# Isolate_IO_v_1.net
KiCad netlist of a schematic drawn in EAGLE
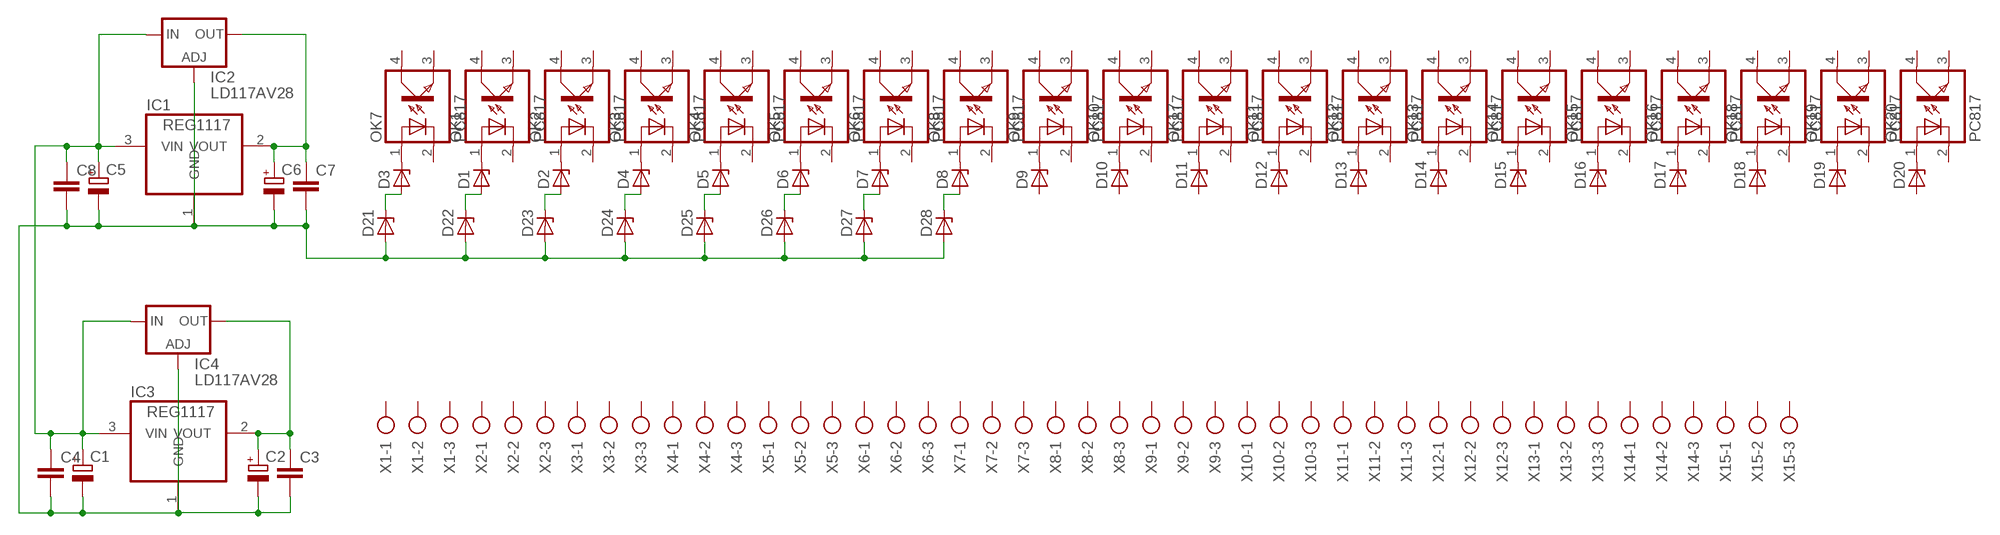
[diagram p0: schematic, sheet 1]

(export (version "E")
  (design (tool "Eeschema 10.0.6"))
  (components
    (comp (ref "C1")
      (value "CPOL-EUE2.5-5")
      (footprint "eagle-import:E2,5-5")
      (libsource (lib "eagle-import") (part "CPOL-EUE2.5-5"))
    )
    (comp (ref "C2")
      (value "CPOL-EUE3.5-10")
      (footprint "eagle-import:E3,5-10")
      (libsource (lib "eagle-import") (part "CPOL-EUE3.5-10"))
    )
    (comp (ref "C3")
      (value "C-EU025-030X050")
      (footprint "eagle-import:C025-030X050")
      (libsource (lib "eagle-import") (part "C-EU025-030X050"))
    )
    (comp (ref "C4")
      (value "C-EU025-030X050")
      (footprint "eagle-import:C025-030X050")
      (libsource (lib "eagle-import") (part "C-EU025-030X050"))
    )
    (comp (ref "C5")
      (value "CPOL-EUE2.5-5")
      (footprint "eagle-import:E2,5-5")
      (libsource (lib "eagle-import") (part "CPOL-EUE2.5-5"))
    )
    (comp (ref "C6")
      (value "CPOL-EUE3.5-10")
      (footprint "eagle-import:E3,5-10")
      (libsource (lib "eagle-import") (part "CPOL-EUE3.5-10"))
    )
    (comp (ref "C7")
      (value "C-EU025-030X050")
      (footprint "eagle-import:C025-030X050")
      (libsource (lib "eagle-import") (part "C-EU025-030X050"))
    )
    (comp (ref "C8")
      (value "C-EU025-030X050")
      (footprint "eagle-import:C025-030X050")
      (libsource (lib "eagle-import") (part "C-EU025-030X050"))
    )
    (comp (ref "D1")
      (value "ZENER-DIODEZD-2.5")
      (footprint "eagle-import:ZDIO-2.5")
      (libsource (lib "eagle-import") (part "ZENER-DIODEZD-2.5"))
    )
    (comp (ref "D2")
      (value "ZENER-DIODEZD-2.5")
      (footprint "eagle-import:ZDIO-2.5")
      (libsource (lib "eagle-import") (part "ZENER-DIODEZD-2.5"))
    )
    (comp (ref "D3")
      (value "ZENER-DIODEZD-2.5")
      (footprint "eagle-import:ZDIO-2.5")
      (libsource (lib "eagle-import") (part "ZENER-DIODEZD-2.5"))
    )
    (comp (ref "D4")
      (value "ZENER-DIODEZD-2.5")
      (footprint "eagle-import:ZDIO-2.5")
      (libsource (lib "eagle-import") (part "ZENER-DIODEZD-2.5"))
    )
    (comp (ref "D5")
      (value "ZENER-DIODEZD-2.5")
      (footprint "eagle-import:ZDIO-2.5")
      (libsource (lib "eagle-import") (part "ZENER-DIODEZD-2.5"))
    )
    (comp (ref "D6")
      (value "ZENER-DIODEZD-2.5")
      (footprint "eagle-import:ZDIO-2.5")
      (libsource (lib "eagle-import") (part "ZENER-DIODEZD-2.5"))
    )
    (comp (ref "D7")
      (value "ZENER-DIODEZD-2.5")
      (footprint "eagle-import:ZDIO-2.5")
      (libsource (lib "eagle-import") (part "ZENER-DIODEZD-2.5"))
    )
    (comp (ref "D8")
      (value "ZENER-DIODEZD-2.5")
      (footprint "eagle-import:ZDIO-2.5")
      (libsource (lib "eagle-import") (part "ZENER-DIODEZD-2.5"))
    )
    (comp (ref "D9")
      (value "ZENER-DIODEZD-2.5")
      (footprint "eagle-import:ZDIO-2.5")
      (libsource (lib "eagle-import") (part "ZENER-DIODEZD-2.5"))
    )
    (comp (ref "D10")
      (value "ZENER-DIODEZD-2.5")
      (footprint "eagle-import:ZDIO-2.5")
      (libsource (lib "eagle-import") (part "ZENER-DIODEZD-2.5"))
    )
    (comp (ref "D11")
      (value "ZENER-DIODEZD-2.5")
      (footprint "eagle-import:ZDIO-2.5")
      (libsource (lib "eagle-import") (part "ZENER-DIODEZD-2.5"))
    )
    (comp (ref "D12")
      (value "ZENER-DIODEZD-2.5")
      (footprint "eagle-import:ZDIO-2.5")
      (libsource (lib "eagle-import") (part "ZENER-DIODEZD-2.5"))
    )
    (comp (ref "D13")
      (value "ZENER-DIODEZD-2.5")
      (footprint "eagle-import:ZDIO-2.5")
      (libsource (lib "eagle-import") (part "ZENER-DIODEZD-2.5"))
    )
    (comp (ref "D14")
      (value "ZENER-DIODEZD-2.5")
      (footprint "eagle-import:ZDIO-2.5")
      (libsource (lib "eagle-import") (part "ZENER-DIODEZD-2.5"))
    )
    (comp (ref "D15")
      (value "ZENER-DIODEZD-2.5")
      (footprint "eagle-import:ZDIO-2.5")
      (libsource (lib "eagle-import") (part "ZENER-DIODEZD-2.5"))
    )
    (comp (ref "D16")
      (value "ZENER-DIODEZD-2.5")
      (footprint "eagle-import:ZDIO-2.5")
      (libsource (lib "eagle-import") (part "ZENER-DIODEZD-2.5"))
    )
    (comp (ref "D17")
      (value "ZENER-DIODEZD-2.5")
      (footprint "eagle-import:ZDIO-2.5")
      (libsource (lib "eagle-import") (part "ZENER-DIODEZD-2.5"))
    )
    (comp (ref "D18")
      (value "ZENER-DIODEZD-2.5")
      (footprint "eagle-import:ZDIO-2.5")
      (libsource (lib "eagle-import") (part "ZENER-DIODEZD-2.5"))
    )
    (comp (ref "D19")
      (value "ZENER-DIODEZD-2.5")
      (footprint "eagle-import:ZDIO-2.5")
      (libsource (lib "eagle-import") (part "ZENER-DIODEZD-2.5"))
    )
    (comp (ref "D20")
      (value "ZENER-DIODEZD-2.5")
      (footprint "eagle-import:ZDIO-2.5")
      (libsource (lib "eagle-import") (part "ZENER-DIODEZD-2.5"))
    )
    (comp (ref "D21")
      (value "ZENER-DIODEZD-2.5")
      (footprint "eagle-import:ZDIO-2.5")
      (libsource (lib "eagle-import") (part "ZENER-DIODEZD-2.5"))
    )
    (comp (ref "D22")
      (value "ZENER-DIODEZD-2.5")
      (footprint "eagle-import:ZDIO-2.5")
      (libsource (lib "eagle-import") (part "ZENER-DIODEZD-2.5"))
    )
    (comp (ref "D23")
      (value "ZENER-DIODEZD-2.5")
      (footprint "eagle-import:ZDIO-2.5")
      (libsource (lib "eagle-import") (part "ZENER-DIODEZD-2.5"))
    )
    (comp (ref "D24")
      (value "ZENER-DIODEZD-2.5")
      (footprint "eagle-import:ZDIO-2.5")
      (libsource (lib "eagle-import") (part "ZENER-DIODEZD-2.5"))
    )
    (comp (ref "D25")
      (value "ZENER-DIODEZD-2.5")
      (footprint "eagle-import:ZDIO-2.5")
      (libsource (lib "eagle-import") (part "ZENER-DIODEZD-2.5"))
    )
    (comp (ref "D26")
      (value "ZENER-DIODEZD-2.5")
      (footprint "eagle-import:ZDIO-2.5")
      (libsource (lib "eagle-import") (part "ZENER-DIODEZD-2.5"))
    )
    (comp (ref "D27")
      (value "ZENER-DIODEZD-2.5")
      (footprint "eagle-import:ZDIO-2.5")
      (libsource (lib "eagle-import") (part "ZENER-DIODEZD-2.5"))
    )
    (comp (ref "D28")
      (value "ZENER-DIODEZD-2.5")
      (footprint "eagle-import:ZDIO-2.5")
      (libsource (lib "eagle-import") (part "ZENER-DIODEZD-2.5"))
    )
    (comp (ref "IC1")
      (value "REG1117")
      (footprint "eagle-import:SOT223")
      (libsource (lib "eagle-import") (part "REG1117"))
    )
    (comp (ref "IC2")
      (value "LD117AV28")
      (footprint "eagle-import:TO220L1")
      (libsource (lib "eagle-import") (part "LD117A?V28"))
    )
    (comp (ref "IC3")
      (value "REG1117")
      (footprint "eagle-import:SOT223")
      (libsource (lib "eagle-import") (part "REG1117"))
    )
    (comp (ref "IC4")
      (value "LD117AV28")
      (footprint "eagle-import:TO220L1")
      (libsource (lib "eagle-import") (part "LD117A?V28"))
    )
    (comp (ref "OK1")
      (value "PC817")
      (footprint "eagle-import:DIL04")
      (fields (field (name "MPN") "PC817X4J000F"))
      (libsource (lib "eagle-import") (part "PC817"))
    )
    (comp (ref "OK2")
      (value "PC817")
      (footprint "eagle-import:DIL04")
      (fields (field (name "MPN") "PC817X4J000F"))
      (libsource (lib "eagle-import") (part "PC817"))
    )
    (comp (ref "OK3")
      (value "PC817")
      (footprint "eagle-import:DIL04")
      (fields (field (name "MPN") "PC817X4J000F"))
      (libsource (lib "eagle-import") (part "PC817"))
    )
    (comp (ref "OK4")
      (value "PC817")
      (footprint "eagle-import:DIL04")
      (fields (field (name "MPN") "PC817X4J000F"))
      (libsource (lib "eagle-import") (part "PC817"))
    )
    (comp (ref "OK5")
      (value "PC817")
      (footprint "eagle-import:DIL04")
      (fields (field (name "MPN") "PC817X4J000F"))
      (libsource (lib "eagle-import") (part "PC817"))
    )
    (comp (ref "OK6")
      (value "PC817")
      (footprint "eagle-import:DIL04")
      (fields (field (name "MPN") "PC817X4J000F"))
      (libsource (lib "eagle-import") (part "PC817"))
    )
    (comp (ref "OK7")
      (value "PC817")
      (footprint "eagle-import:DIL04")
      (fields (field (name "MPN") "PC817X4J000F"))
      (libsource (lib "eagle-import") (part "PC817"))
    )
    (comp (ref "OK8")
      (value "PC817")
      (footprint "eagle-import:DIL04")
      (fields (field (name "MPN") "PC817X4J000F"))
      (libsource (lib "eagle-import") (part "PC817"))
    )
    (comp (ref "OK9")
      (value "PC817")
      (footprint "eagle-import:DIL04")
      (fields (field (name "MPN") "PC817X4J000F"))
      (libsource (lib "eagle-import") (part "PC817"))
    )
    (comp (ref "OK10")
      (value "PC817")
      (footprint "eagle-import:DIL04")
      (fields (field (name "MPN") "PC817X4J000F"))
      (libsource (lib "eagle-import") (part "PC817"))
    )
    (comp (ref "OK11")
      (value "PC817")
      (footprint "eagle-import:DIL04")
      (fields (field (name "MPN") "PC817X4J000F"))
      (libsource (lib "eagle-import") (part "PC817"))
    )
    (comp (ref "OK12")
      (value "PC817")
      (footprint "eagle-import:DIL04")
      (fields (field (name "MPN") "PC817X4J000F"))
      (libsource (lib "eagle-import") (part "PC817"))
    )
    (comp (ref "OK13")
      (value "PC817")
      (footprint "eagle-import:DIL04")
      (fields (field (name "MPN") "PC817X4J000F"))
      (libsource (lib "eagle-import") (part "PC817"))
    )
    (comp (ref "OK14")
      (value "PC817")
      (footprint "eagle-import:DIL04")
      (fields (field (name "MPN") "PC817X4J000F"))
      (libsource (lib "eagle-import") (part "PC817"))
    )
    (comp (ref "OK15")
      (value "PC817")
      (footprint "eagle-import:DIL04")
      (fields (field (name "MPN") "PC817X4J000F"))
      (libsource (lib "eagle-import") (part "PC817"))
    )
    (comp (ref "OK16")
      (value "PC817")
      (footprint "eagle-import:DIL04")
      (fields (field (name "MPN") "PC817X4J000F"))
      (libsource (lib "eagle-import") (part "PC817"))
    )
    (comp (ref "OK17")
      (value "PC817")
      (footprint "eagle-import:DIL04")
      (fields (field (name "MPN") "PC817X4J000F"))
      (libsource (lib "eagle-import") (part "PC817"))
    )
    (comp (ref "OK18")
      (value "PC817")
      (footprint "eagle-import:DIL04")
      (fields (field (name "MPN") "PC817X4J000F"))
      (libsource (lib "eagle-import") (part "PC817"))
    )
    (comp (ref "OK19")
      (value "PC817")
      (footprint "eagle-import:DIL04")
      (fields (field (name "MPN") "PC817X4J000F"))
      (libsource (lib "eagle-import") (part "PC817"))
    )
    (comp (ref "OK20")
      (value "PC817")
      (footprint "eagle-import:DIL04")
      (fields (field (name "MPN") "PC817X4J000F"))
      (libsource (lib "eagle-import") (part "PC817"))
    )
    (comp (ref "X1")
      (value "AK500/3")
      (footprint "eagle-import:AK500_3")
      (libsource (lib "eagle-import") (part "AK500/3"))
    )
    (comp (ref "X2")
      (value "AK500/3")
      (footprint "eagle-import:AK500_3")
      (libsource (lib "eagle-import") (part "AK500/3"))
    )
    (comp (ref "X3")
      (value "AK500/3")
      (footprint "eagle-import:AK500_3")
      (libsource (lib "eagle-import") (part "AK500/3"))
    )
    (comp (ref "X4")
      (value "AK500/3")
      (footprint "eagle-import:AK500_3")
      (libsource (lib "eagle-import") (part "AK500/3"))
    )
    (comp (ref "X5")
      (value "AK500/3")
      (footprint "eagle-import:AK500_3")
      (libsource (lib "eagle-import") (part "AK500/3"))
    )
    (comp (ref "X6")
      (value "AK500/3")
      (footprint "eagle-import:AK500_3")
      (libsource (lib "eagle-import") (part "AK500/3"))
    )
    (comp (ref "X7")
      (value "AK500/3")
      (footprint "eagle-import:AK500_3")
      (libsource (lib "eagle-import") (part "AK500/3"))
    )
    (comp (ref "X8")
      (value "AK500/3")
      (footprint "eagle-import:AK500_3")
      (libsource (lib "eagle-import") (part "AK500/3"))
    )
    (comp (ref "X9")
      (value "AK500/3")
      (footprint "eagle-import:AK500_3")
      (libsource (lib "eagle-import") (part "AK500/3"))
    )
    (comp (ref "X10")
      (value "AK500/3")
      (footprint "eagle-import:AK500_3")
      (libsource (lib "eagle-import") (part "AK500/3"))
    )
    (comp (ref "X11")
      (value "AK500/3")
      (footprint "eagle-import:AK500_3")
      (libsource (lib "eagle-import") (part "AK500/3"))
    )
    (comp (ref "X12")
      (value "AK500/3")
      (footprint "eagle-import:AK500_3")
      (libsource (lib "eagle-import") (part "AK500/3"))
    )
    (comp (ref "X13")
      (value "AK500/3")
      (footprint "eagle-import:AK500_3")
      (libsource (lib "eagle-import") (part "AK500/3"))
    )
    (comp (ref "X14")
      (value "AK500/3")
      (footprint "eagle-import:AK500_3")
      (libsource (lib "eagle-import") (part "AK500/3"))
    )
    (comp (ref "X15")
      (value "AK500/3")
      (footprint "eagle-import:AK500_3")
      (libsource (lib "eagle-import") (part "AK500/3"))
    )
  )
  (nets
    (net (code "1") (name "Net-(D1-PadA)") (class "Default")
      (node (ref "D1") (pin "A") (pinfunction "A_A") (pintype "passive"))
      (node (ref "D22") (pin "C") (pinfunction "C_C") (pintype "passive"))
    )
    (net (code "2") (name "Net-(D2-PadA)") (class "Default")
      (node (ref "D2") (pin "A") (pinfunction "A_A") (pintype "passive"))
      (node (ref "D23") (pin "C") (pinfunction "C_C") (pintype "passive"))
    )
    (net (code "3") (name "Net-(D21-PadC)") (class "Default")
      (node (ref "D21") (pin "C") (pinfunction "C_C") (pintype "passive"))
      (node (ref "D3") (pin "A") (pinfunction "A_A") (pintype "passive"))
    )
    (net (code "4") (name "Net-(D24-PadC)") (class "Default")
      (node (ref "D24") (pin "C") (pinfunction "C_C") (pintype "passive"))
      (node (ref "D4") (pin "A") (pinfunction "A_A") (pintype "passive"))
    )
    (net (code "5") (name "Net-(D25-PadC)") (class "Default")
      (node (ref "D25") (pin "C") (pinfunction "C_C") (pintype "passive"))
      (node (ref "D5") (pin "A") (pinfunction "A_A") (pintype "passive"))
    )
    (net (code "6") (name "Net-(D26-PadC)") (class "Default")
      (node (ref "D26") (pin "C") (pinfunction "C_C") (pintype "passive"))
      (node (ref "D6") (pin "A") (pinfunction "A_A") (pintype "passive"))
    )
    (net (code "7") (name "Net-(D27-PadC)") (class "Default")
      (node (ref "D27") (pin "C") (pinfunction "C_C") (pintype "passive"))
      (node (ref "D7") (pin "A") (pinfunction "A_A") (pintype "passive"))
    )
    (net (code "8") (name "Net-(D28-PadC)") (class "Default")
      (node (ref "D28") (pin "C") (pinfunction "C_C") (pintype "passive"))
      (node (ref "D8") (pin "A") (pinfunction "A_A") (pintype "passive"))
    )
    (net (code "9") (name "Net-(IC1-GND)") (class "Default")
      (node (ref "C1") (pin "-") (pinfunction "-_-") (pintype "passive"))
      (node (ref "C2") (pin "-") (pinfunction "-_-") (pintype "passive"))
      (node (ref "C3") (pin "2") (pinfunction "2_2") (pintype "passive"))
      (node (ref "C4") (pin "2") (pinfunction "2_2") (pintype "passive"))
      (node (ref "C5") (pin "-") (pinfunction "-_-") (pintype "passive"))
      (node (ref "C6") (pin "-") (pinfunction "-_-") (pintype "passive"))
      (node (ref "C7") (pin "2") (pinfunction "2_2") (pintype "passive"))
      (node (ref "C8") (pin "2") (pinfunction "2_2") (pintype "passive"))
      (node (ref "D21") (pin "A") (pinfunction "A_A") (pintype "passive"))
      (node (ref "D22") (pin "A") (pinfunction "A_A") (pintype "passive"))
      (node (ref "D23") (pin "A") (pinfunction "A_A") (pintype "passive"))
      (node (ref "D24") (pin "A") (pinfunction "A_A") (pintype "passive"))
      (node (ref "D25") (pin "A") (pinfunction "A_A") (pintype "passive"))
      (node (ref "D26") (pin "A") (pinfunction "A_A") (pintype "passive"))
      (node (ref "D27") (pin "A") (pinfunction "A_A") (pintype "passive"))
      (node (ref "D28") (pin "A") (pinfunction "A_A") (pintype "passive"))
      (node (ref "IC1") (pin "1") (pinfunction "GND_1") (pintype "power_in"))
      (node (ref "IC2") (pin "1") (pinfunction "ADJ_1") (pintype "input"))
      (node (ref "IC3") (pin "1") (pinfunction "GND_1") (pintype "power_in"))
      (node (ref "IC4") (pin "1") (pinfunction "ADJ_1") (pintype "input"))
    )
    (net (code "10") (name "Net-(IC1-VIN)") (class "Default")
      (node (ref "C1") (pin "+") (pinfunction "+_+") (pintype "passive"))
      (node (ref "C4") (pin "1") (pinfunction "1_1") (pintype "passive"))
      (node (ref "C5") (pin "+") (pinfunction "+_+") (pintype "passive"))
      (node (ref "C8") (pin "1") (pinfunction "1_1") (pintype "passive"))
      (node (ref "IC1") (pin "3") (pinfunction "VIN_3") (pintype "input"))
      (node (ref "IC2") (pin "3") (pinfunction "IN_3") (pintype "input"))
      (node (ref "IC3") (pin "3") (pinfunction "VIN_3") (pintype "input"))
      (node (ref "IC4") (pin "3") (pinfunction "IN_3") (pintype "input"))
    )
    (net (code "11") (name "Net-(IC1-VOUT)") (class "Default")
      (node (ref "C6") (pin "+") (pinfunction "+_+") (pintype "passive"))
      (node (ref "C7") (pin "1") (pinfunction "1_1") (pintype "passive"))
      (node (ref "IC1") (pin "2") (pinfunction "VOUT_2") (pintype "output"))
      (node (ref "IC2") (pin "2") (pinfunction "OUT_2") (pintype "passive"))
    )
    (net (code "12") (name "Net-(IC3-VOUT)") (class "Default")
      (node (ref "C2") (pin "+") (pinfunction "+_+") (pintype "passive"))
      (node (ref "C3") (pin "1") (pinfunction "1_1") (pintype "passive"))
      (node (ref "IC3") (pin "2") (pinfunction "VOUT_2") (pintype "output"))
      (node (ref "IC4") (pin "2") (pinfunction "OUT_2") (pintype "passive"))
    )
    (net (code "13") (name "Net-(OK1-A)") (class "Default")
      (node (ref "D1") (pin "C") (pinfunction "C_C") (pintype "passive"))
      (node (ref "OK1") (pin "1") (pinfunction "A_1") (pintype "passive"))
    )
    (net (code "14") (name "Net-(OK2-A)") (class "Default")
      (node (ref "D2") (pin "C") (pinfunction "C_C") (pintype "passive"))
      (node (ref "OK2") (pin "1") (pinfunction "A_1") (pintype "passive"))
    )
    (net (code "15") (name "Net-(OK3-A)") (class "Default")
      (node (ref "D4") (pin "C") (pinfunction "C_C") (pintype "passive"))
      (node (ref "OK3") (pin "1") (pinfunction "A_1") (pintype "passive"))
    )
    (net (code "16") (name "Net-(OK4-A)") (class "Default")
      (node (ref "D5") (pin "C") (pinfunction "C_C") (pintype "passive"))
      (node (ref "OK4") (pin "1") (pinfunction "A_1") (pintype "passive"))
    )
    (net (code "17") (name "Net-(OK5-A)") (class "Default")
      (node (ref "D6") (pin "C") (pinfunction "C_C") (pintype "passive"))
      (node (ref "OK5") (pin "1") (pinfunction "A_1") (pintype "passive"))
    )
    (net (code "18") (name "Net-(OK6-A)") (class "Default")
      (node (ref "D7") (pin "C") (pinfunction "C_C") (pintype "passive"))
      (node (ref "OK6") (pin "1") (pinfunction "A_1") (pintype "passive"))
    )
    (net (code "19") (name "Net-(OK7-A)") (class "Default")
      (node (ref "D3") (pin "C") (pinfunction "C_C") (pintype "passive"))
      (node (ref "OK7") (pin "1") (pinfunction "A_1") (pintype "passive"))
    )
    (net (code "20") (name "Net-(OK8-A)") (class "Default")
      (node (ref "D8") (pin "C") (pinfunction "C_C") (pintype "passive"))
      (node (ref "OK8") (pin "1") (pinfunction "A_1") (pintype "passive"))
    )
    (net (code "21") (name "Net-(OK9-A)") (class "Default")
      (node (ref "D9") (pin "C") (pinfunction "C_C") (pintype "passive"))
      (node (ref "OK9") (pin "1") (pinfunction "A_1") (pintype "passive"))
    )
    (net (code "22") (name "Net-(OK10-A)") (class "Default")
      (node (ref "D10") (pin "C") (pinfunction "C_C") (pintype "passive"))
      (node (ref "OK10") (pin "1") (pinfunction "A_1") (pintype "passive"))
    )
    (net (code "23") (name "Net-(OK11-A)") (class "Default")
      (node (ref "D12") (pin "C") (pinfunction "C_C") (pintype "passive"))
      (node (ref "OK11") (pin "1") (pinfunction "A_1") (pintype "passive"))
    )
    (net (code "24") (name "Net-(OK12-A)") (class "Default")
      (node (ref "D13") (pin "C") (pinfunction "C_C") (pintype "passive"))
      (node (ref "OK12") (pin "1") (pinfunction "A_1") (pintype "passive"))
    )
    (net (code "25") (name "Net-(OK13-A)") (class "Default")
      (node (ref "D14") (pin "C") (pinfunction "C_C") (pintype "passive"))
      (node (ref "OK13") (pin "1") (pinfunction "A_1") (pintype "passive"))
    )
    (net (code "26") (name "Net-(OK14-A)") (class "Default")
      (node (ref "D15") (pin "C") (pinfunction "C_C") (pintype "passive"))
      (node (ref "OK14") (pin "1") (pinfunction "A_1") (pintype "passive"))
    )
    (net (code "27") (name "Net-(OK15-A)") (class "Default")
      (node (ref "D16") (pin "C") (pinfunction "C_C") (pintype "passive"))
      (node (ref "OK15") (pin "1") (pinfunction "A_1") (pintype "passive"))
    )
    (net (code "28") (name "Net-(OK16-A)") (class "Default")
      (node (ref "D17") (pin "C") (pinfunction "C_C") (pintype "passive"))
      (node (ref "OK16") (pin "1") (pinfunction "A_1") (pintype "passive"))
    )
    (net (code "29") (name "Net-(OK17-A)") (class "Default")
      (node (ref "D11") (pin "C") (pinfunction "C_C") (pintype "passive"))
      (node (ref "OK17") (pin "1") (pinfunction "A_1") (pintype "passive"))
    )
    (net (code "30") (name "Net-(OK18-A)") (class "Default")
      (node (ref "D18") (pin "C") (pinfunction "C_C") (pintype "passive"))
      (node (ref "OK18") (pin "1") (pinfunction "A_1") (pintype "passive"))
    )
    (net (code "31") (name "Net-(OK19-A)") (class "Default")
      (node (ref "D19") (pin "C") (pinfunction "C_C") (pintype "passive"))
      (node (ref "OK19") (pin "1") (pinfunction "A_1") (pintype "passive"))
    )
    (net (code "32") (name "Net-(OK20-A)") (class "Default")
      (node (ref "D20") (pin "C") (pinfunction "C_C") (pintype "passive"))
      (node (ref "OK20") (pin "1") (pinfunction "A_1") (pintype "passive"))
    )
    (net (code "33") (name "unconnected-(D9-PadA)") (class "Default")
      (node (ref "D9") (pin "A") (pinfunction "A_A") (pintype "passive"))
    )
    (net (code "34") (name "unconnected-(D10-PadA)") (class "Default")
      (node (ref "D10") (pin "A") (pinfunction "A_A") (pintype "passive"))
    )
    (net (code "35") (name "unconnected-(D11-PadA)") (class "Default")
      (node (ref "D11") (pin "A") (pinfunction "A_A") (pintype "passive"))
    )
    (net (code "36") (name "unconnected-(D12-PadA)") (class "Default")
      (node (ref "D12") (pin "A") (pinfunction "A_A") (pintype "passive"))
    )
    (net (code "37") (name "unconnected-(D13-PadA)") (class "Default")
      (node (ref "D13") (pin "A") (pinfunction "A_A") (pintype "passive"))
    )
    (net (code "38") (name "unconnected-(D14-PadA)") (class "Default")
      (node (ref "D14") (pin "A") (pinfunction "A_A") (pintype "passive"))
    )
    (net (code "39") (name "unconnected-(D15-PadA)") (class "Default")
      (node (ref "D15") (pin "A") (pinfunction "A_A") (pintype "passive"))
    )
    (net (code "40") (name "unconnected-(D16-PadA)") (class "Default")
      (node (ref "D16") (pin "A") (pinfunction "A_A") (pintype "passive"))
    )
    (net (code "41") (name "unconnected-(D17-PadA)") (class "Default")
      (node (ref "D17") (pin "A") (pinfunction "A_A") (pintype "passive"))
    )
    (net (code "42") (name "unconnected-(D18-PadA)") (class "Default")
      (node (ref "D18") (pin "A") (pinfunction "A_A") (pintype "passive"))
    )
    (net (code "43") (name "unconnected-(D19-PadA)") (class "Default")
      (node (ref "D19") (pin "A") (pinfunction "A_A") (pintype "passive"))
    )
    (net (code "44") (name "unconnected-(D20-PadA)") (class "Default")
      (node (ref "D20") (pin "A") (pinfunction "A_A") (pintype "passive"))
    )
    (net (code "45") (name "unconnected-(OK1-C-Pad2)") (class "Default")
      (node (ref "OK1") (pin "2") (pinfunction "C_2") (pintype "passive"))
    )
    (net (code "46") (name "unconnected-(OK1-COL-Pad4)") (class "Default")
      (node (ref "OK1") (pin "4") (pinfunction "COL_4") (pintype "passive"))
    )
    (net (code "47") (name "unconnected-(OK1-EMIT-Pad3)") (class "Default")
      (node (ref "OK1") (pin "3") (pinfunction "EMIT_3") (pintype "passive"))
    )
    (net (code "48") (name "unconnected-(OK2-C-Pad2)") (class "Default")
      (node (ref "OK2") (pin "2") (pinfunction "C_2") (pintype "passive"))
    )
    (net (code "49") (name "unconnected-(OK2-COL-Pad4)") (class "Default")
      (node (ref "OK2") (pin "4") (pinfunction "COL_4") (pintype "passive"))
    )
    (net (code "50") (name "unconnected-(OK2-EMIT-Pad3)") (class "Default")
      (node (ref "OK2") (pin "3") (pinfunction "EMIT_3") (pintype "passive"))
    )
    (net (code "51") (name "unconnected-(OK3-C-Pad2)") (class "Default")
      (node (ref "OK3") (pin "2") (pinfunction "C_2") (pintype "passive"))
    )
    (net (code "52") (name "unconnected-(OK3-COL-Pad4)") (class "Default")
      (node (ref "OK3") (pin "4") (pinfunction "COL_4") (pintype "passive"))
    )
    (net (code "53") (name "unconnected-(OK3-EMIT-Pad3)") (class "Default")
      (node (ref "OK3") (pin "3") (pinfunction "EMIT_3") (pintype "passive"))
    )
    (net (code "54") (name "unconnected-(OK4-C-Pad2)") (class "Default")
      (node (ref "OK4") (pin "2") (pinfunction "C_2") (pintype "passive"))
    )
    (net (code "55") (name "unconnected-(OK4-COL-Pad4)") (class "Default")
      (node (ref "OK4") (pin "4") (pinfunction "COL_4") (pintype "passive"))
    )
    (net (code "56") (name "unconnected-(OK4-EMIT-Pad3)") (class "Default")
      (node (ref "OK4") (pin "3") (pinfunction "EMIT_3") (pintype "passive"))
    )
    (net (code "57") (name "unconnected-(OK5-C-Pad2)") (class "Default")
      (node (ref "OK5") (pin "2") (pinfunction "C_2") (pintype "passive"))
    )
    (net (code "58") (name "unconnected-(OK5-COL-Pad4)") (class "Default")
      (node (ref "OK5") (pin "4") (pinfunction "COL_4") (pintype "passive"))
    )
    (net (code "59") (name "unconnected-(OK5-EMIT-Pad3)") (class "Default")
      (node (ref "OK5") (pin "3") (pinfunction "EMIT_3") (pintype "passive"))
    )
    (net (code "60") (name "unconnected-(OK6-C-Pad2)") (class "Default")
      (node (ref "OK6") (pin "2") (pinfunction "C_2") (pintype "passive"))
    )
    (net (code "61") (name "unconnected-(OK6-COL-Pad4)") (class "Default")
      (node (ref "OK6") (pin "4") (pinfunction "COL_4") (pintype "passive"))
    )
    (net (code "62") (name "unconnected-(OK6-EMIT-Pad3)") (class "Default")
      (node (ref "OK6") (pin "3") (pinfunction "EMIT_3") (pintype "passive"))
    )
    (net (code "63") (name "unconnected-(OK7-C-Pad2)") (class "Default")
      (node (ref "OK7") (pin "2") (pinfunction "C_2") (pintype "passive"))
    )
    (net (code "64") (name "unconnected-(OK7-COL-Pad4)") (class "Default")
      (node (ref "OK7") (pin "4") (pinfunction "COL_4") (pintype "passive"))
    )
    (net (code "65") (name "unconnected-(OK7-EMIT-Pad3)") (class "Default")
      (node (ref "OK7") (pin "3") (pinfunction "EMIT_3") (pintype "passive"))
    )
    (net (code "66") (name "unconnected-(OK8-C-Pad2)") (class "Default")
      (node (ref "OK8") (pin "2") (pinfunction "C_2") (pintype "passive"))
    )
    (net (code "67") (name "unconnected-(OK8-COL-Pad4)") (class "Default")
      (node (ref "OK8") (pin "4") (pinfunction "COL_4") (pintype "passive"))
    )
    (net (code "68") (name "unconnected-(OK8-EMIT-Pad3)") (class "Default")
      (node (ref "OK8") (pin "3") (pinfunction "EMIT_3") (pintype "passive"))
    )
    (net (code "69") (name "unconnected-(OK9-C-Pad2)") (class "Default")
      (node (ref "OK9") (pin "2") (pinfunction "C_2") (pintype "passive"))
    )
    (net (code "70") (name "unconnected-(OK9-COL-Pad4)") (class "Default")
      (node (ref "OK9") (pin "4") (pinfunction "COL_4") (pintype "passive"))
    )
    (net (code "71") (name "unconnected-(OK9-EMIT-Pad3)") (class "Default")
      (node (ref "OK9") (pin "3") (pinfunction "EMIT_3") (pintype "passive"))
    )
    (net (code "72") (name "unconnected-(OK10-C-Pad2)") (class "Default")
      (node (ref "OK10") (pin "2") (pinfunction "C_2") (pintype "passive"))
    )
    (net (code "73") (name "unconnected-(OK10-COL-Pad4)") (class "Default")
      (node (ref "OK10") (pin "4") (pinfunction "COL_4") (pintype "passive"))
    )
    (net (code "74") (name "unconnected-(OK10-EMIT-Pad3)") (class "Default")
      (node (ref "OK10") (pin "3") (pinfunction "EMIT_3") (pintype "passive"))
    )
    (net (code "75") (name "unconnected-(OK11-C-Pad2)") (class "Default")
      (node (ref "OK11") (pin "2") (pinfunction "C_2") (pintype "passive"))
    )
    (net (code "76") (name "unconnected-(OK11-COL-Pad4)") (class "Default")
      (node (ref "OK11") (pin "4") (pinfunction "COL_4") (pintype "passive"))
    )
    (net (code "77") (name "unconnected-(OK11-EMIT-Pad3)") (class "Default")
      (node (ref "OK11") (pin "3") (pinfunction "EMIT_3") (pintype "passive"))
    )
    (net (code "78") (name "unconnected-(OK12-C-Pad2)") (class "Default")
      (node (ref "OK12") (pin "2") (pinfunction "C_2") (pintype "passive"))
    )
    (net (code "79") (name "unconnected-(OK12-COL-Pad4)") (class "Default")
      (node (ref "OK12") (pin "4") (pinfunction "COL_4") (pintype "passive"))
    )
    (net (code "80") (name "unconnected-(OK12-EMIT-Pad3)") (class "Default")
      (node (ref "OK12") (pin "3") (pinfunction "EMIT_3") (pintype "passive"))
    )
    (net (code "81") (name "unconnected-(OK13-C-Pad2)") (class "Default")
      (node (ref "OK13") (pin "2") (pinfunction "C_2") (pintype "passive"))
    )
    (net (code "82") (name "unconnected-(OK13-COL-Pad4)") (class "Default")
      (node (ref "OK13") (pin "4") (pinfunction "COL_4") (pintype "passive"))
    )
    (net (code "83") (name "unconnected-(OK13-EMIT-Pad3)") (class "Default")
      (node (ref "OK13") (pin "3") (pinfunction "EMIT_3") (pintype "passive"))
    )
    (net (code "84") (name "unconnected-(OK14-C-Pad2)") (class "Default")
      (node (ref "OK14") (pin "2") (pinfunction "C_2") (pintype "passive"))
    )
    (net (code "85") (name "unconnected-(OK14-COL-Pad4)") (class "Default")
      (node (ref "OK14") (pin "4") (pinfunction "COL_4") (pintype "passive"))
    )
    (net (code "86") (name "unconnected-(OK14-EMIT-Pad3)") (class "Default")
      (node (ref "OK14") (pin "3") (pinfunction "EMIT_3") (pintype "passive"))
    )
    (net (code "87") (name "unconnected-(OK15-C-Pad2)") (class "Default")
      (node (ref "OK15") (pin "2") (pinfunction "C_2") (pintype "passive"))
    )
    (net (code "88") (name "unconnected-(OK15-COL-Pad4)") (class "Default")
      (node (ref "OK15") (pin "4") (pinfunction "COL_4") (pintype "passive"))
    )
    (net (code "89") (name "unconnected-(OK15-EMIT-Pad3)") (class "Default")
      (node (ref "OK15") (pin "3") (pinfunction "EMIT_3") (pintype "passive"))
    )
    (net (code "90") (name "unconnected-(OK16-C-Pad2)") (class "Default")
      (node (ref "OK16") (pin "2") (pinfunction "C_2") (pintype "passive"))
    )
    (net (code "91") (name "unconnected-(OK16-COL-Pad4)") (class "Default")
      (node (ref "OK16") (pin "4") (pinfunction "COL_4") (pintype "passive"))
    )
    (net (code "92") (name "unconnected-(OK16-EMIT-Pad3)") (class "Default")
      (node (ref "OK16") (pin "3") (pinfunction "EMIT_3") (pintype "passive"))
    )
    (net (code "93") (name "unconnected-(OK17-C-Pad2)") (class "Default")
      (node (ref "OK17") (pin "2") (pinfunction "C_2") (pintype "passive"))
    )
    (net (code "94") (name "unconnected-(OK17-COL-Pad4)") (class "Default")
      (node (ref "OK17") (pin "4") (pinfunction "COL_4") (pintype "passive"))
    )
    (net (code "95") (name "unconnected-(OK17-EMIT-Pad3)") (class "Default")
      (node (ref "OK17") (pin "3") (pinfunction "EMIT_3") (pintype "passive"))
    )
    (net (code "96") (name "unconnected-(OK18-C-Pad2)") (class "Default")
      (node (ref "OK18") (pin "2") (pinfunction "C_2") (pintype "passive"))
    )
    (net (code "97") (name "unconnected-(OK18-COL-Pad4)") (class "Default")
      (node (ref "OK18") (pin "4") (pinfunction "COL_4") (pintype "passive"))
    )
    (net (code "98") (name "unconnected-(OK18-EMIT-Pad3)") (class "Default")
      (node (ref "OK18") (pin "3") (pinfunction "EMIT_3") (pintype "passive"))
    )
    (net (code "99") (name "unconnected-(OK19-C-Pad2)") (class "Default")
      (node (ref "OK19") (pin "2") (pinfunction "C_2") (pintype "passive"))
    )
    (net (code "100") (name "unconnected-(OK19-COL-Pad4)") (class "Default")
      (node (ref "OK19") (pin "4") (pinfunction "COL_4") (pintype "passive"))
    )
    (net (code "101") (name "unconnected-(OK19-EMIT-Pad3)") (class "Default")
      (node (ref "OK19") (pin "3") (pinfunction "EMIT_3") (pintype "passive"))
    )
    (net (code "102") (name "unconnected-(OK20-C-Pad2)") (class "Default")
      (node (ref "OK20") (pin "2") (pinfunction "C_2") (pintype "passive"))
    )
    (net (code "103") (name "unconnected-(OK20-COL-Pad4)") (class "Default")
      (node (ref "OK20") (pin "4") (pinfunction "COL_4") (pintype "passive"))
    )
    (net (code "104") (name "unconnected-(OK20-EMIT-Pad3)") (class "Default")
      (node (ref "OK20") (pin "3") (pinfunction "EMIT_3") (pintype "passive"))
    )
    (net (code "105") (name "unconnected-(X1A-KL-Pad1)") (class "Default")
      (node (ref "X1") (pin "1") (pinfunction "KL_1") (pintype "passive"))
    )
    (net (code "106") (name "unconnected-(X1B-KL-Pad2)") (class "Default")
      (node (ref "X1") (pin "2") (pinfunction "KL_2") (pintype "passive"))
    )
    (net (code "107") (name "unconnected-(X1C-KL-Pad3)") (class "Default")
      (node (ref "X1") (pin "3") (pinfunction "KL_3") (pintype "passive"))
    )
    (net (code "108") (name "unconnected-(X2A-KL-Pad1)") (class "Default")
      (node (ref "X2") (pin "1") (pinfunction "KL_1") (pintype "passive"))
    )
    (net (code "109") (name "unconnected-(X2B-KL-Pad2)") (class "Default")
      (node (ref "X2") (pin "2") (pinfunction "KL_2") (pintype "passive"))
    )
    (net (code "110") (name "unconnected-(X2C-KL-Pad3)") (class "Default")
      (node (ref "X2") (pin "3") (pinfunction "KL_3") (pintype "passive"))
    )
    (net (code "111") (name "unconnected-(X3A-KL-Pad1)") (class "Default")
      (node (ref "X3") (pin "1") (pinfunction "KL_1") (pintype "passive"))
    )
    (net (code "112") (name "unconnected-(X3B-KL-Pad2)") (class "Default")
      (node (ref "X3") (pin "2") (pinfunction "KL_2") (pintype "passive"))
    )
    (net (code "113") (name "unconnected-(X3C-KL-Pad3)") (class "Default")
      (node (ref "X3") (pin "3") (pinfunction "KL_3") (pintype "passive"))
    )
    (net (code "114") (name "unconnected-(X4A-KL-Pad1)") (class "Default")
      (node (ref "X4") (pin "1") (pinfunction "KL_1") (pintype "passive"))
    )
    (net (code "115") (name "unconnected-(X4B-KL-Pad2)") (class "Default")
      (node (ref "X4") (pin "2") (pinfunction "KL_2") (pintype "passive"))
    )
    (net (code "116") (name "unconnected-(X4C-KL-Pad3)") (class "Default")
      (node (ref "X4") (pin "3") (pinfunction "KL_3") (pintype "passive"))
    )
    (net (code "117") (name "unconnected-(X5A-KL-Pad1)") (class "Default")
      (node (ref "X5") (pin "1") (pinfunction "KL_1") (pintype "passive"))
    )
    (net (code "118") (name "unconnected-(X5B-KL-Pad2)") (class "Default")
      (node (ref "X5") (pin "2") (pinfunction "KL_2") (pintype "passive"))
    )
    (net (code "119") (name "unconnected-(X5C-KL-Pad3)") (class "Default")
      (node (ref "X5") (pin "3") (pinfunction "KL_3") (pintype "passive"))
    )
    (net (code "120") (name "unconnected-(X6A-KL-Pad1)") (class "Default")
      (node (ref "X6") (pin "1") (pinfunction "KL_1") (pintype "passive"))
    )
    (net (code "121") (name "unconnected-(X6B-KL-Pad2)") (class "Default")
      (node (ref "X6") (pin "2") (pinfunction "KL_2") (pintype "passive"))
    )
    (net (code "122") (name "unconnected-(X6C-KL-Pad3)") (class "Default")
      (node (ref "X6") (pin "3") (pinfunction "KL_3") (pintype "passive"))
    )
    (net (code "123") (name "unconnected-(X7A-KL-Pad1)") (class "Default")
      (node (ref "X7") (pin "1") (pinfunction "KL_1") (pintype "passive"))
    )
    (net (code "124") (name "unconnected-(X7B-KL-Pad2)") (class "Default")
      (node (ref "X7") (pin "2") (pinfunction "KL_2") (pintype "passive"))
    )
    (net (code "125") (name "unconnected-(X7C-KL-Pad3)") (class "Default")
      (node (ref "X7") (pin "3") (pinfunction "KL_3") (pintype "passive"))
    )
    (net (code "126") (name "unconnected-(X8A-KL-Pad1)") (class "Default")
      (node (ref "X8") (pin "1") (pinfunction "KL_1") (pintype "passive"))
    )
    (net (code "127") (name "unconnected-(X8B-KL-Pad2)") (class "Default")
      (node (ref "X8") (pin "2") (pinfunction "KL_2") (pintype "passive"))
    )
    (net (code "128") (name "unconnected-(X8C-KL-Pad3)") (class "Default")
      (node (ref "X8") (pin "3") (pinfunction "KL_3") (pintype "passive"))
    )
    (net (code "129") (name "unconnected-(X9A-KL-Pad1)") (class "Default")
      (node (ref "X9") (pin "1") (pinfunction "KL_1") (pintype "passive"))
    )
    (net (code "130") (name "unconnected-(X9B-KL-Pad2)") (class "Default")
      (node (ref "X9") (pin "2") (pinfunction "KL_2") (pintype "passive"))
    )
    (net (code "131") (name "unconnected-(X9C-KL-Pad3)") (class "Default")
      (node (ref "X9") (pin "3") (pinfunction "KL_3") (pintype "passive"))
    )
    (net (code "132") (name "unconnected-(X10A-KL-Pad1)") (class "Default")
      (node (ref "X10") (pin "1") (pinfunction "KL_1") (pintype "passive"))
    )
    (net (code "133") (name "unconnected-(X10B-KL-Pad2)") (class "Default")
      (node (ref "X10") (pin "2") (pinfunction "KL_2") (pintype "passive"))
    )
    (net (code "134") (name "unconnected-(X10C-KL-Pad3)") (class "Default")
      (node (ref "X10") (pin "3") (pinfunction "KL_3") (pintype "passive"))
    )
    (net (code "135") (name "unconnected-(X11A-KL-Pad1)") (class "Default")
      (node (ref "X11") (pin "1") (pinfunction "KL_1") (pintype "passive"))
    )
    (net (code "136") (name "unconnected-(X11B-KL-Pad2)") (class "Default")
      (node (ref "X11") (pin "2") (pinfunction "KL_2") (pintype "passive"))
    )
    (net (code "137") (name "unconnected-(X11C-KL-Pad3)") (class "Default")
      (node (ref "X11") (pin "3") (pinfunction "KL_3") (pintype "passive"))
    )
    (net (code "138") (name "unconnected-(X12A-KL-Pad1)") (class "Default")
      (node (ref "X12") (pin "1") (pinfunction "KL_1") (pintype "passive"))
    )
    (net (code "139") (name "unconnected-(X12B-KL-Pad2)") (class "Default")
      (node (ref "X12") (pin "2") (pinfunction "KL_2") (pintype "passive"))
    )
    (net (code "140") (name "unconnected-(X12C-KL-Pad3)") (class "Default")
      (node (ref "X12") (pin "3") (pinfunction "KL_3") (pintype "passive"))
    )
    (net (code "141") (name "unconnected-(X13A-KL-Pad1)") (class "Default")
      (node (ref "X13") (pin "1") (pinfunction "KL_1") (pintype "passive"))
    )
    (net (code "142") (name "unconnected-(X13B-KL-Pad2)") (class "Default")
      (node (ref "X13") (pin "2") (pinfunction "KL_2") (pintype "passive"))
    )
    (net (code "143") (name "unconnected-(X13C-KL-Pad3)") (class "Default")
      (node (ref "X13") (pin "3") (pinfunction "KL_3") (pintype "passive"))
    )
    (net (code "144") (name "unconnected-(X14A-KL-Pad1)") (class "Default")
      (node (ref "X14") (pin "1") (pinfunction "KL_1") (pintype "passive"))
    )
    (net (code "145") (name "unconnected-(X14B-KL-Pad2)") (class "Default")
      (node (ref "X14") (pin "2") (pinfunction "KL_2") (pintype "passive"))
    )
    (net (code "146") (name "unconnected-(X14C-KL-Pad3)") (class "Default")
      (node (ref "X14") (pin "3") (pinfunction "KL_3") (pintype "passive"))
    )
    (net (code "147") (name "unconnected-(X15A-KL-Pad1)") (class "Default")
      (node (ref "X15") (pin "1") (pinfunction "KL_1") (pintype "passive"))
    )
    (net (code "148") (name "unconnected-(X15B-KL-Pad2)") (class "Default")
      (node (ref "X15") (pin "2") (pinfunction "KL_2") (pintype "passive"))
    )
    (net (code "149") (name "unconnected-(X15C-KL-Pad3)") (class "Default")
      (node (ref "X15") (pin "3") (pinfunction "KL_3") (pintype "passive"))
    )
  )
)
